# ReflowController_true_rev2.net
KiCad netlist of a schematic drawn in EAGLE
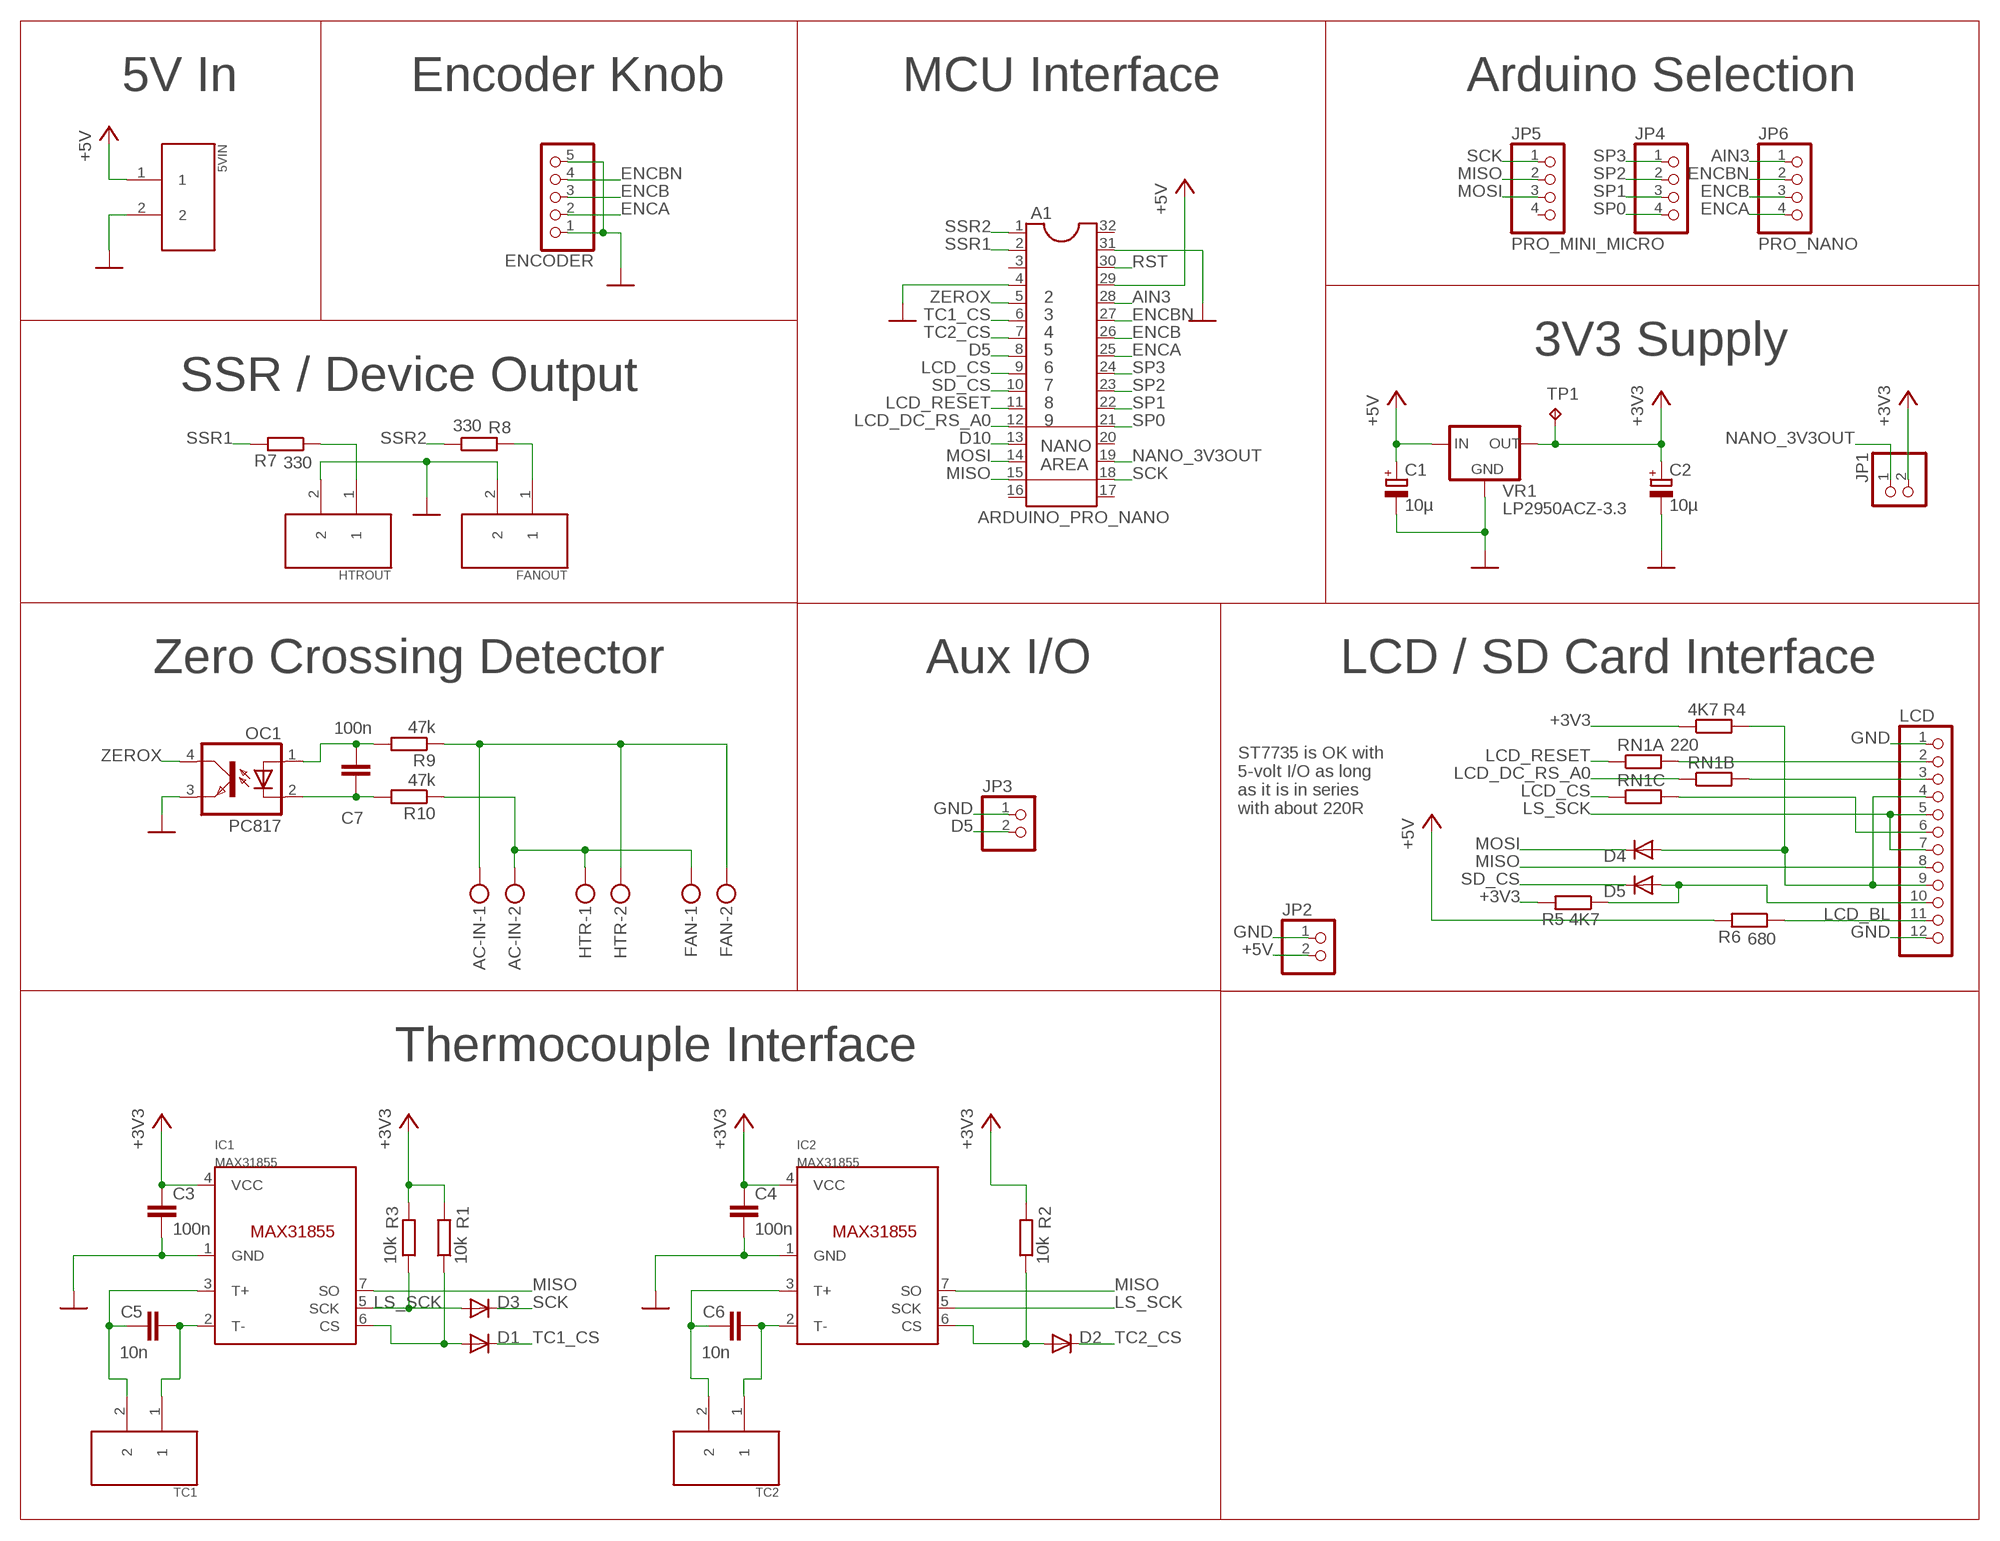
[diagram p0: schematic, sheet 1]

(export (version "E")
  (design (tool "Eeschema 10.0.6"))
  (components
    (comp (ref "5VIN")
      (value "WECO_110-M-221/2")
      (footprint "eagle-import:WECO-PHOENIXTERM-2-POS")
      (libsource (lib "eagle-import") (part "WECO_110-M-221/2"))
    )
    (comp (ref "A1")
      (value "ARDUINO_PRO_NANO")
      (footprint "eagle-import:DIL32")
      (libsource (lib "eagle-import") (part "DIL32"))
    )
    (comp (ref "AC-IN")
      (value "MKDSN1,5/2-5,08")
      (footprint "eagle-import:MKDSN1,5_2-5,08")
      (fields (field (name "MPN") "MKDSN 1,5/2-5.08"))
      (libsource (lib "eagle-import") (part "MKDSN1,5/2-5,08"))
    )
    (comp (ref "C1")
      (value "10µ")
      (footprint "eagle-import:C_6032-28R")
      (libsource (lib "eagle-import") (part "CPOL-EUC/6032-28R"))
    )
    (comp (ref "C2")
      (value "10µ")
      (footprint "eagle-import:C_6032-28R")
      (libsource (lib "eagle-import") (part "CPOL-EUC/6032-28R"))
    )
    (comp (ref "C3")
      (value "100n")
      (footprint "eagle-import:C0805")
      (libsource (lib "eagle-import") (part "C-EUC0805"))
    )
    (comp (ref "C4")
      (value "100n")
      (footprint "eagle-import:C0805")
      (libsource (lib "eagle-import") (part "C-EUC0805"))
    )
    (comp (ref "C5")
      (value "10n")
      (footprint "eagle-import:C0805")
      (libsource (lib "eagle-import") (part "C-EUC0805"))
    )
    (comp (ref "C6")
      (value "10n")
      (footprint "eagle-import:C0805")
      (libsource (lib "eagle-import") (part "C-EUC0805"))
    )
    (comp (ref "C7")
      (value "100n")
      (footprint "eagle-import:C150-054X183")
      (libsource (lib "eagle-import") (part "C-EU150-054X183"))
    )
    (comp (ref "D1")
      (value "DIODESOD-123")
      (footprint "eagle-import:SOD-123")
      (libsource (lib "eagle-import") (part "DIODESOD-123"))
    )
    (comp (ref "D2")
      (value "DIODESOD-123")
      (footprint "eagle-import:SOD-123")
      (libsource (lib "eagle-import") (part "DIODESOD-123"))
    )
    (comp (ref "D3")
      (value "DIODESOD-123")
      (footprint "eagle-import:SOD-123")
      (libsource (lib "eagle-import") (part "DIODESOD-123"))
    )
    (comp (ref "D4")
      (value "DIODESOD-123")
      (footprint "eagle-import:SOD-123")
      (libsource (lib "eagle-import") (part "DIODESOD-123"))
    )
    (comp (ref "D5")
      (value "DIODESOD-123")
      (footprint "eagle-import:SOD-123")
      (libsource (lib "eagle-import") (part "DIODESOD-123"))
    )
    (comp (ref "ENCODER")
      (value "PINHD-1X5")
      (footprint "eagle-import:1X05")
      (libsource (lib "eagle-import") (part "PINHD-1X5"))
    )
    (comp (ref "FAN")
      (value "MKDSN1,5/2-5,08")
      (footprint "eagle-import:MKDSN1,5_2-5,08")
      (fields (field (name "MPN") "MKDSN 1,5/2-5.08"))
      (libsource (lib "eagle-import") (part "MKDSN1,5/2-5,08"))
    )
    (comp (ref "FANOUT")
      (value "WECO_110-M-221/2")
      (footprint "eagle-import:WECO-PHOENIXTERM-2-POS")
      (libsource (lib "eagle-import") (part "WECO_110-M-221/2"))
    )
    (comp (ref "HTR")
      (value "MKDSN1,5/2-5,08")
      (footprint "eagle-import:MKDSN1,5_2-5,08")
      (fields (field (name "MPN") "MKDSN 1,5/2-5.08"))
      (libsource (lib "eagle-import") (part "MKDSN1,5/2-5,08"))
    )
    (comp (ref "HTROUT")
      (value "WECO_110-M-221/2")
      (footprint "eagle-import:WECO-PHOENIXTERM-2-POS")
      (libsource (lib "eagle-import") (part "WECO_110-M-221/2"))
    )
    (comp (ref "IC1")
      (value "MAX31855")
      (footprint "eagle-import:SOIC8")
      (libsource (lib "eagle-import") (part "MAX31855"))
    )
    (comp (ref "IC2")
      (value "MAX31855")
      (footprint "eagle-import:SOIC8")
      (libsource (lib "eagle-import") (part "MAX31855"))
    )
    (comp (ref "JP1")
      (value "PINHD-1X2")
      (footprint "eagle-import:1X02")
      (libsource (lib "eagle-import") (part "PINHD-1X2"))
    )
    (comp (ref "JP2")
      (value "PINHD-1X2")
      (footprint "eagle-import:1X02")
      (libsource (lib "eagle-import") (part "PINHD-1X2"))
    )
    (comp (ref "JP3")
      (value "PINHD-1X2")
      (footprint "eagle-import:1X02")
      (libsource (lib "eagle-import") (part "PINHD-1X2"))
    )
    (comp (ref "JP4")
      (value "PINHD-1X4RND")
      (footprint "eagle-import:1X04_RND")
      (libsource (lib "eagle-import") (part "PINHD-1X4RND"))
    )
    (comp (ref "JP5")
      (value "PRO_MINI_MICRO")
      (footprint "eagle-import:1X04_RND")
      (libsource (lib "eagle-import") (part "PINHD-1X4RND"))
    )
    (comp (ref "JP6")
      (value "PRO_NANO")
      (footprint "eagle-import:1X04_RND")
      (libsource (lib "eagle-import") (part "PINHD-1X4RND"))
    )
    (comp (ref "LCD")
      (value "PINHD-1X12")
      (footprint "eagle-import:1X12")
      (libsource (lib "eagle-import") (part "PINHD-1X12"))
    )
    (comp (ref "OC1")
      (value "PC817")
      (footprint "eagle-import:DIL04")
      (fields (field (name "MPN") "PC817X4J000F"))
      (libsource (lib "eagle-import") (part "PC817"))
    )
    (comp (ref "R1")
      (value "10k")
      (footprint "eagle-import:R0805")
      (libsource (lib "eagle-import") (part "R-EU_R0805"))
    )
    (comp (ref "R2")
      (value "10k")
      (footprint "eagle-import:R0805")
      (libsource (lib "eagle-import") (part "R-EU_R0805"))
    )
    (comp (ref "R3")
      (value "10k")
      (footprint "eagle-import:R0805")
      (libsource (lib "eagle-import") (part "R-EU_R0805"))
    )
    (comp (ref "R4")
      (value "4K7")
      (footprint "eagle-import:R0805")
      (libsource (lib "eagle-import") (part "R-EU_R0805"))
    )
    (comp (ref "R5")
      (value "4K7")
      (footprint "eagle-import:R0805")
      (libsource (lib "eagle-import") (part "R-EU_R0805"))
    )
    (comp (ref "R6")
      (value "680")
      (footprint "eagle-import:R0805")
      (libsource (lib "eagle-import") (part "R-EU_R0805"))
    )
    (comp (ref "R7")
      (value "330")
      (footprint "eagle-import:R0805")
      (libsource (lib "eagle-import") (part "R-EU_R0805"))
    )
    (comp (ref "R8")
      (value "330")
      (footprint "eagle-import:R0805")
      (libsource (lib "eagle-import") (part "R-EU_R0805"))
    )
    (comp (ref "R9")
      (value "47k")
      (footprint "eagle-import:0207_5V")
      (libsource (lib "eagle-import") (part "R-EU_0207/5V"))
    )
    (comp (ref "R10")
      (value "47k")
      (footprint "eagle-import:0207_5V")
      (libsource (lib "eagle-import") (part "R-EU_0207/5V"))
    )
    (comp (ref "RN1")
      (value "220")
      (footprint "eagle-import:RN8P-4R-CRA06S")
      (libsource (lib "eagle-import") (part "RESISTOR_ARRAY_4"))
    )
    (comp (ref "TC1")
      (value "WECO_110-M-221/2")
      (footprint "eagle-import:WECO-PHOENIXTERM-2-POS")
      (libsource (lib "eagle-import") (part "WECO_110-M-221/2"))
    )
    (comp (ref "TC2")
      (value "WECO_110-M-221/2")
      (footprint "eagle-import:WECO-PHOENIXTERM-2-POS")
      (libsource (lib "eagle-import") (part "WECO_110-M-221/2"))
    )
    (comp (ref "TP1")
      (value "TPTP08R")
      (footprint "eagle-import:TP08R")
      (libsource (lib "eagle-import") (part "TPTP08R"))
    )
    (comp (ref "VR1")
      (value "LP2950ACZ-3.3")
      (footprint "eagle-import:TO92")
      (libsource (lib "eagle-import") (part "LP2950?ACZ-3.3"))
    )
  )
  (nets
    (net (code "1") (name "+3V3") (class "Default")
      (node (ref "C2") (pin "+") (pinfunction "+_+") (pintype "passive"))
      (node (ref "C3") (pin "1") (pinfunction "1_1") (pintype "passive"))
      (node (ref "C4") (pin "1") (pinfunction "1_1") (pintype "passive"))
      (node (ref "IC1") (pin "4") (pinfunction "VCC_4") (pintype "power_in"))
      (node (ref "IC2") (pin "4") (pinfunction "VCC_4") (pintype "power_in"))
      (node (ref "JP1") (pin "2") (pinfunction "2_2") (pintype "passive"))
      (node (ref "R1") (pin "2") (pinfunction "2_2") (pintype "passive"))
      (node (ref "R2") (pin "2") (pinfunction "2_2") (pintype "passive"))
      (node (ref "R3") (pin "2") (pinfunction "2_2") (pintype "passive"))
      (node (ref "R4") (pin "1") (pinfunction "1_1") (pintype "passive"))
      (node (ref "R5") (pin "2") (pinfunction "2_2") (pintype "passive"))
      (node (ref "TP1") (pin "TP") (pinfunction "TP_TP") (pintype "input"))
      (node (ref "VR1") (pin "1") (pinfunction "OUT_1") (pintype "passive"))
    )
    (net (code "2") (name "+5V") (class "Default")
      (node (ref "5VIN") (pin "1") (pinfunction "1_1") (pintype "bidirectional"))
      (node (ref "A1") (pin "29") (pinfunction "29_29") (pintype "passive"))
      (node (ref "C1") (pin "+") (pinfunction "+_+") (pintype "passive"))
      (node (ref "JP2") (pin "2") (pinfunction "2_2") (pintype "passive"))
      (node (ref "R6") (pin "2") (pinfunction "2_2") (pintype "passive"))
      (node (ref "VR1") (pin "3") (pinfunction "IN_3") (pintype "input"))
    )
    (net (code "3") (name "/AIN3") (class "Default")
      (node (ref "A1") (pin "28") (pinfunction "28_28") (pintype "passive"))
      (node (ref "JP6") (pin "1") (pinfunction "1_1") (pintype "passive"))
    )
    (net (code "4") (name "/D5") (class "Default")
      (node (ref "A1") (pin "8") (pinfunction "8_8") (pintype "passive"))
      (node (ref "JP3") (pin "2") (pinfunction "2_2") (pintype "passive"))
    )
    (net (code "5") (name "/D10") (class "Default")
      (node (ref "A1") (pin "13") (pinfunction "13_13") (pintype "passive"))
    )
    (net (code "6") (name "/ENCA") (class "Default")
      (node (ref "A1") (pin "25") (pinfunction "25_25") (pintype "passive"))
      (node (ref "ENCODER") (pin "2") (pinfunction "2_2") (pintype "passive"))
      (node (ref "JP6") (pin "4") (pinfunction "4_4") (pintype "passive"))
    )
    (net (code "7") (name "/ENCB") (class "Default")
      (node (ref "A1") (pin "26") (pinfunction "26_26") (pintype "passive"))
      (node (ref "ENCODER") (pin "3") (pinfunction "3_3") (pintype "passive"))
      (node (ref "JP6") (pin "3") (pinfunction "3_3") (pintype "passive"))
    )
    (net (code "8") (name "/ENCBN") (class "Default")
      (node (ref "A1") (pin "27") (pinfunction "27_27") (pintype "passive"))
      (node (ref "ENCODER") (pin "4") (pinfunction "4_4") (pintype "passive"))
      (node (ref "JP6") (pin "2") (pinfunction "2_2") (pintype "passive"))
    )
    (net (code "9") (name "/LCD_BL") (class "Default")
      (node (ref "LCD") (pin "11") (pinfunction "11_11") (pintype "passive"))
      (node (ref "R6") (pin "1") (pinfunction "1_1") (pintype "passive"))
    )
    (net (code "10") (name "/LCD_CS") (class "Default")
      (node (ref "A1") (pin "9") (pinfunction "9_9") (pintype "passive"))
      (node (ref "RN1") (pin "3") (pinfunction "1_3") (pintype "passive"))
    )
    (net (code "11") (name "/LCD_DC_RS_A0") (class "Default")
      (node (ref "A1") (pin "12") (pinfunction "12_12") (pintype "passive"))
      (node (ref "RN1") (pin "2") (pinfunction "1_2") (pintype "passive"))
    )
    (net (code "12") (name "/LCD_RESET") (class "Default")
      (node (ref "A1") (pin "11") (pinfunction "11_11") (pintype "passive"))
      (node (ref "RN1") (pin "1") (pinfunction "1_1") (pintype "passive"))
    )
    (net (code "13") (name "/LS_SCK") (class "Default")
      (node (ref "D3") (pin "A") (pinfunction "A_A") (pintype "passive"))
      (node (ref "IC1") (pin "5") (pinfunction "SCK_5") (pintype "input"))
      (node (ref "IC2") (pin "5") (pinfunction "SCK_5") (pintype "input"))
      (node (ref "LCD") (pin "5") (pinfunction "5_5") (pintype "passive"))
      (node (ref "LCD") (pin "7") (pinfunction "7_7") (pintype "passive"))
      (node (ref "R3") (pin "1") (pinfunction "1_1") (pintype "passive"))
    )
    (net (code "14") (name "/MISO") (class "Default")
      (node (ref "A1") (pin "15") (pinfunction "15_15") (pintype "passive"))
      (node (ref "IC1") (pin "7") (pinfunction "SO_7") (pintype "output"))
      (node (ref "IC2") (pin "7") (pinfunction "SO_7") (pintype "output"))
      (node (ref "JP5") (pin "2") (pinfunction "2_2") (pintype "passive"))
      (node (ref "LCD") (pin "8") (pinfunction "8_8") (pintype "passive"))
    )
    (net (code "15") (name "/MOSI") (class "Default")
      (node (ref "A1") (pin "14") (pinfunction "14_14") (pintype "passive"))
      (node (ref "D4") (pin "C") (pinfunction "C_C") (pintype "passive"))
      (node (ref "JP5") (pin "3") (pinfunction "3_3") (pintype "passive"))
    )
    (net (code "16") (name "/NANO_3V3OUT") (class "Default")
      (node (ref "A1") (pin "19") (pinfunction "19_19") (pintype "passive"))
      (node (ref "JP1") (pin "1") (pinfunction "1_1") (pintype "passive"))
    )
    (net (code "17") (name "/RST") (class "Default")
      (node (ref "A1") (pin "30") (pinfunction "30_30") (pintype "passive"))
    )
    (net (code "18") (name "/SCK") (class "Default")
      (node (ref "A1") (pin "18") (pinfunction "18_18") (pintype "passive"))
      (node (ref "D3") (pin "C") (pinfunction "C_C") (pintype "passive"))
      (node (ref "JP5") (pin "1") (pinfunction "1_1") (pintype "passive"))
    )
    (net (code "19") (name "/SD_CS") (class "Default")
      (node (ref "A1") (pin "10") (pinfunction "10_10") (pintype "passive"))
      (node (ref "D5") (pin "C") (pinfunction "C_C") (pintype "passive"))
    )
    (net (code "20") (name "/SP0") (class "Default")
      (node (ref "A1") (pin "21") (pinfunction "21_21") (pintype "passive"))
      (node (ref "JP4") (pin "4") (pinfunction "4_4") (pintype "passive"))
    )
    (net (code "21") (name "/SP1") (class "Default")
      (node (ref "A1") (pin "22") (pinfunction "22_22") (pintype "passive"))
      (node (ref "JP4") (pin "3") (pinfunction "3_3") (pintype "passive"))
    )
    (net (code "22") (name "/SP2") (class "Default")
      (node (ref "A1") (pin "23") (pinfunction "23_23") (pintype "passive"))
      (node (ref "JP4") (pin "2") (pinfunction "2_2") (pintype "passive"))
    )
    (net (code "23") (name "/SP3") (class "Default")
      (node (ref "A1") (pin "24") (pinfunction "24_24") (pintype "passive"))
      (node (ref "JP4") (pin "1") (pinfunction "1_1") (pintype "passive"))
    )
    (net (code "24") (name "/SSR1") (class "Default")
      (node (ref "A1") (pin "2") (pinfunction "2_2") (pintype "passive"))
      (node (ref "R7") (pin "2") (pinfunction "2_2") (pintype "passive"))
    )
    (net (code "25") (name "/SSR2") (class "Default")
      (node (ref "A1") (pin "1") (pinfunction "1_1") (pintype "passive"))
      (node (ref "R8") (pin "1") (pinfunction "1_1") (pintype "passive"))
    )
    (net (code "26") (name "/TC1_CS") (class "Default")
      (node (ref "A1") (pin "6") (pinfunction "6_6") (pintype "passive"))
      (node (ref "D1") (pin "C") (pinfunction "C_C") (pintype "passive"))
    )
    (net (code "27") (name "/TC2_CS") (class "Default")
      (node (ref "A1") (pin "7") (pinfunction "7_7") (pintype "passive"))
      (node (ref "D2") (pin "C") (pinfunction "C_C") (pintype "passive"))
    )
    (net (code "28") (name "/ZEROX") (class "Default")
      (node (ref "A1") (pin "5") (pinfunction "5_5") (pintype "passive"))
      (node (ref "OC1") (pin "4") (pinfunction "COL_4") (pintype "passive"))
    )
    (net (code "29") (name "GND") (class "Default")
      (node (ref "5VIN") (pin "2") (pinfunction "2_2") (pintype "bidirectional"))
      (node (ref "A1") (pin "31") (pinfunction "31_31") (pintype "passive"))
      (node (ref "A1") (pin "4") (pinfunction "4_4") (pintype "passive"))
      (node (ref "C1") (pin "-") (pinfunction "-_-") (pintype "passive"))
      (node (ref "C2") (pin "-") (pinfunction "-_-") (pintype "passive"))
      (node (ref "C3") (pin "2") (pinfunction "2_2") (pintype "passive"))
      (node (ref "C4") (pin "2") (pinfunction "2_2") (pintype "passive"))
      (node (ref "ENCODER") (pin "1") (pinfunction "1_1") (pintype "passive"))
      (node (ref "ENCODER") (pin "5") (pinfunction "5_5") (pintype "passive"))
      (node (ref "FANOUT") (pin "2") (pinfunction "2_2") (pintype "bidirectional"))
      (node (ref "HTROUT") (pin "2") (pinfunction "2_2") (pintype "bidirectional"))
      (node (ref "IC1") (pin "1") (pinfunction "GND_1") (pintype "power_in"))
      (node (ref "IC2") (pin "1") (pinfunction "GND_1") (pintype "power_in"))
      (node (ref "JP2") (pin "1") (pinfunction "1_1") (pintype "passive"))
      (node (ref "JP3") (pin "1") (pinfunction "1_1") (pintype "passive"))
      (node (ref "LCD") (pin "1") (pinfunction "1_1") (pintype "passive"))
      (node (ref "LCD") (pin "12") (pinfunction "12_12") (pintype "passive"))
      (node (ref "OC1") (pin "3") (pinfunction "EMIT_3") (pintype "passive"))
      (node (ref "VR1") (pin "2") (pinfunction "GND_2") (pintype "input"))
    )
    (net (code "30") (name "Net-(AC-INA-KL)") (class "Default")
      (node (ref "AC-IN") (pin "1") (pinfunction "KL_1") (pintype "passive"))
      (node (ref "FAN") (pin "2") (pinfunction "KL_2") (pintype "passive"))
      (node (ref "HTR") (pin "2") (pinfunction "KL_2") (pintype "passive"))
      (node (ref "R9") (pin "1") (pinfunction "1_1") (pintype "passive"))
    )
    (net (code "31") (name "Net-(AC-INB-KL)") (class "Default")
      (node (ref "AC-IN") (pin "2") (pinfunction "KL_2") (pintype "passive"))
      (node (ref "FAN") (pin "1") (pinfunction "KL_1") (pintype "passive"))
      (node (ref "HTR") (pin "1") (pinfunction "KL_1") (pintype "passive"))
      (node (ref "R10") (pin "1") (pinfunction "1_1") (pintype "passive"))
    )
    (net (code "32") (name "Net-(D4-PadA)") (class "Default")
      (node (ref "D4") (pin "A") (pinfunction "A_A") (pintype "passive"))
      (node (ref "LCD") (pin "4") (pinfunction "4_4") (pintype "passive"))
      (node (ref "LCD") (pin "9") (pinfunction "9_9") (pintype "passive"))
      (node (ref "R4") (pin "2") (pinfunction "2_2") (pintype "passive"))
    )
    (net (code "33") (name "Net-(D5-PadA)") (class "Default")
      (node (ref "D5") (pin "A") (pinfunction "A_A") (pintype "passive"))
      (node (ref "LCD") (pin "10") (pinfunction "10_10") (pintype "passive"))
      (node (ref "R5") (pin "1") (pinfunction "1_1") (pintype "passive"))
    )
    (net (code "34") (name "Net-(FANOUT-Pad1)") (class "Default")
      (node (ref "FANOUT") (pin "1") (pinfunction "1_1") (pintype "bidirectional"))
      (node (ref "R8") (pin "2") (pinfunction "2_2") (pintype "passive"))
    )
    (net (code "35") (name "Net-(HTROUT-Pad1)") (class "Default")
      (node (ref "HTROUT") (pin "1") (pinfunction "1_1") (pintype "bidirectional"))
      (node (ref "R7") (pin "1") (pinfunction "1_1") (pintype "passive"))
    )
    (net (code "36") (name "Net-(IC1-CS)") (class "Default")
      (node (ref "D1") (pin "A") (pinfunction "A_A") (pintype "passive"))
      (node (ref "IC1") (pin "6") (pinfunction "CS_6") (pintype "input"))
      (node (ref "R1") (pin "1") (pinfunction "1_1") (pintype "passive"))
    )
    (net (code "37") (name "Net-(IC1-T+)") (class "Default")
      (node (ref "C5") (pin "1") (pinfunction "1_1") (pintype "passive"))
      (node (ref "IC1") (pin "3") (pinfunction "T+_3") (pintype "input"))
      (node (ref "TC1") (pin "2") (pinfunction "2_2") (pintype "bidirectional"))
    )
    (net (code "38") (name "Net-(IC1-T-)") (class "Default")
      (node (ref "C5") (pin "2") (pinfunction "2_2") (pintype "passive"))
      (node (ref "IC1") (pin "2") (pinfunction "T-_2") (pintype "input"))
      (node (ref "TC1") (pin "1") (pinfunction "1_1") (pintype "bidirectional"))
    )
    (net (code "39") (name "Net-(IC2-CS)") (class "Default")
      (node (ref "D2") (pin "A") (pinfunction "A_A") (pintype "passive"))
      (node (ref "IC2") (pin "6") (pinfunction "CS_6") (pintype "input"))
      (node (ref "R2") (pin "1") (pinfunction "1_1") (pintype "passive"))
    )
    (net (code "40") (name "Net-(IC2-T+)") (class "Default")
      (node (ref "C6") (pin "1") (pinfunction "1_1") (pintype "passive"))
      (node (ref "IC2") (pin "3") (pinfunction "T+_3") (pintype "input"))
      (node (ref "TC2") (pin "2") (pinfunction "2_2") (pintype "bidirectional"))
    )
    (net (code "41") (name "Net-(IC2-T-)") (class "Default")
      (node (ref "C6") (pin "2") (pinfunction "2_2") (pintype "passive"))
      (node (ref "IC2") (pin "2") (pinfunction "T-_2") (pintype "input"))
      (node (ref "TC2") (pin "1") (pinfunction "1_1") (pintype "bidirectional"))
    )
    (net (code "42") (name "Net-(OC1-A)") (class "Default")
      (node (ref "C7") (pin "2") (pinfunction "2_2") (pintype "passive"))
      (node (ref "OC1") (pin "1") (pinfunction "A_1") (pintype "passive"))
      (node (ref "R9") (pin "2") (pinfunction "2_2") (pintype "passive"))
    )
    (net (code "43") (name "Net-(OC1-C)") (class "Default")
      (node (ref "C7") (pin "1") (pinfunction "1_1") (pintype "passive"))
      (node (ref "OC1") (pin "2") (pinfunction "C_2") (pintype "passive"))
      (node (ref "R10") (pin "2") (pinfunction "2_2") (pintype "passive"))
    )
    (net (code "44") (name "Net-(RN1A-2)") (class "Default")
      (node (ref "LCD") (pin "2") (pinfunction "2_2") (pintype "passive"))
      (node (ref "RN1") (pin "8") (pinfunction "2_8") (pintype "passive"))
    )
    (net (code "45") (name "Net-(RN1B-2)") (class "Default")
      (node (ref "LCD") (pin "3") (pinfunction "3_3") (pintype "passive"))
      (node (ref "RN1") (pin "7") (pinfunction "2_7") (pintype "passive"))
    )
    (net (code "46") (name "Net-(RN1C-2)") (class "Default")
      (node (ref "LCD") (pin "6") (pinfunction "6_6") (pintype "passive"))
      (node (ref "RN1") (pin "6") (pinfunction "2_6") (pintype "passive"))
    )
    (net (code "47") (name "unconnected-(A1-Pad3)") (class "Default")
      (node (ref "A1") (pin "3") (pinfunction "3_3") (pintype "passive"))
    )
    (net (code "48") (name "unconnected-(A1-Pad16)") (class "Default")
      (node (ref "A1") (pin "16") (pinfunction "16_16") (pintype "passive"))
    )
    (net (code "49") (name "unconnected-(A1-Pad17)") (class "Default")
      (node (ref "A1") (pin "17") (pinfunction "17_17") (pintype "passive"))
    )
    (net (code "50") (name "unconnected-(A1-Pad20)") (class "Default")
      (node (ref "A1") (pin "20") (pinfunction "20_20") (pintype "passive"))
    )
    (net (code "51") (name "unconnected-(A1-Pad32)") (class "Default")
      (node (ref "A1") (pin "32") (pinfunction "32_32") (pintype "passive"))
    )
    (net (code "52") (name "unconnected-(JP5-Pad4)") (class "Default")
      (node (ref "JP5") (pin "4") (pinfunction "4_4") (pintype "passive"))
    )
  )
)
